# Sheet1.net
KiCad netlist of a schematic drawn in Altium Designer
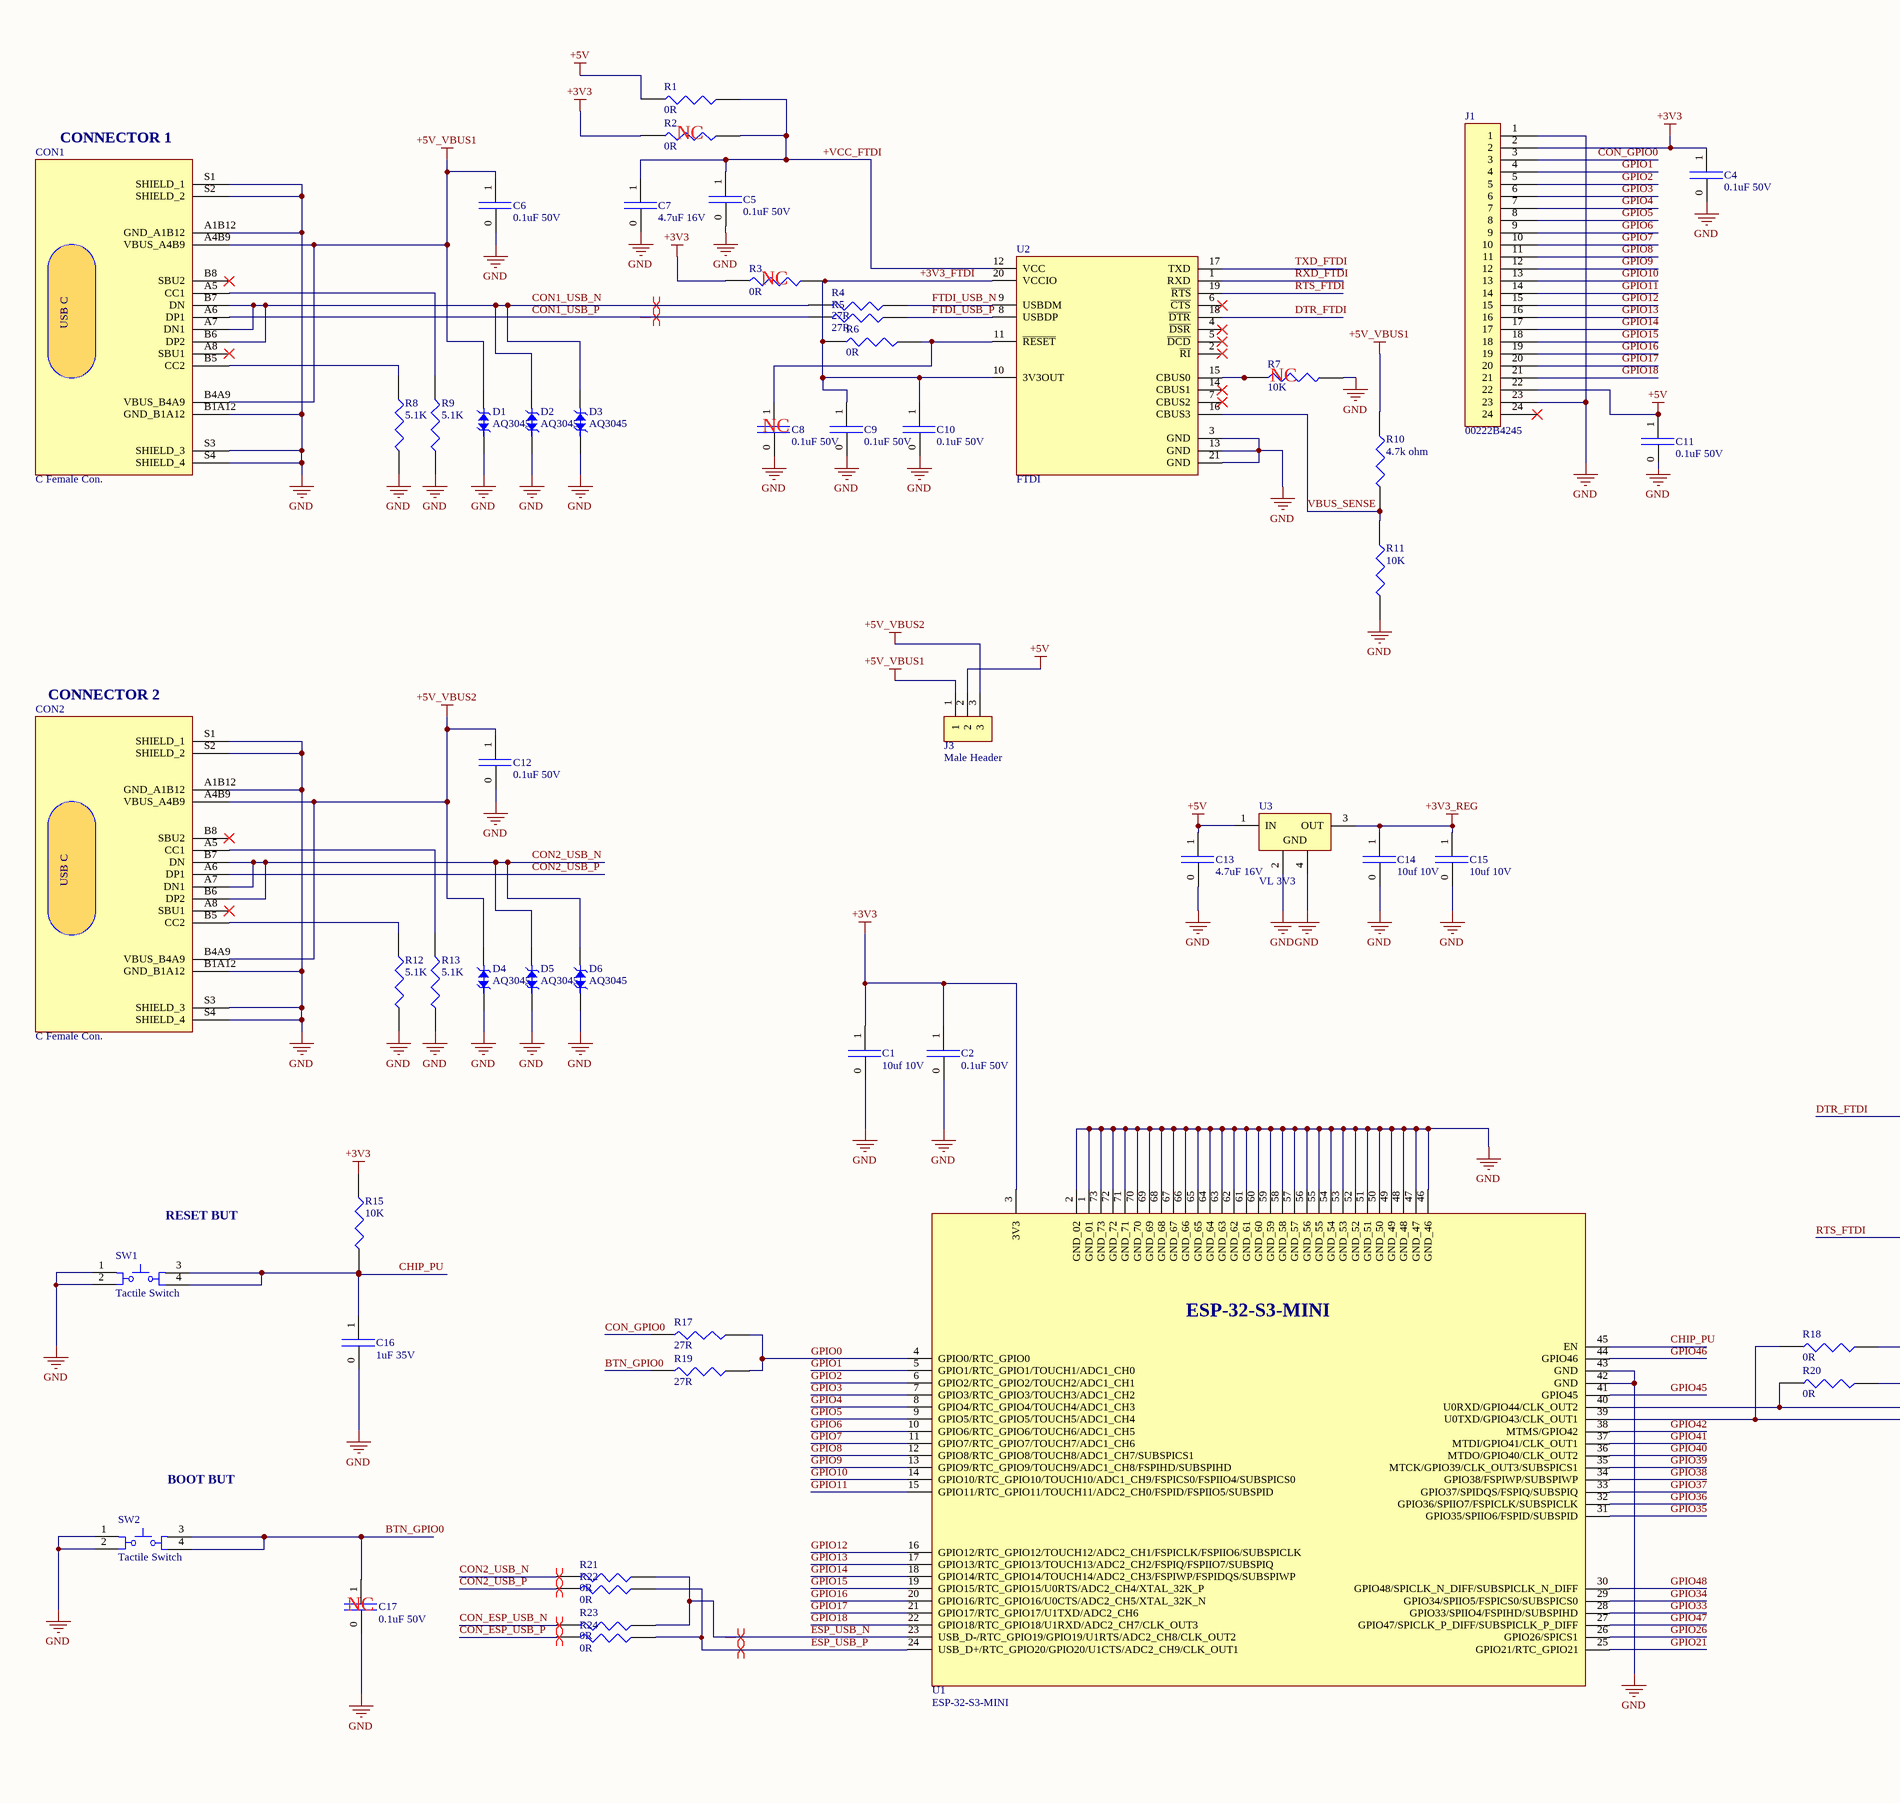
[diagram p0: Sheet1.SchDoc, left]
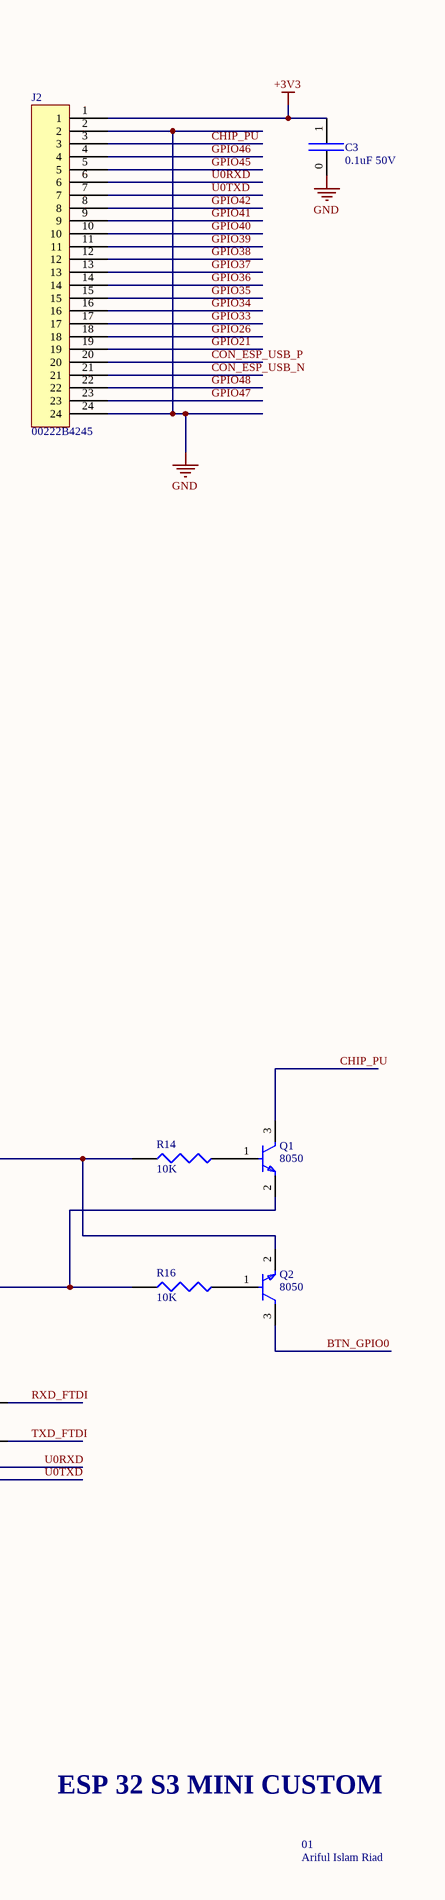
[diagram p1: Sheet1.SchDoc, right]

(export (version "E")
  (design (tool "Eeschema 10.0.6"))
  (components
    (comp (ref "C1")
      (value "10uf 10V")
      (footprint "CAPC1005X80N")
      (fields
        (field (name "MANUFACTURER") "Samsung Electro-Mechanics")
        (field (name "MANUFACTURER PART NUMBER") "CL05A106MP5NUNC")
        (field (name "TOLERANCE") "20%")
      )
      (libsource (lib "Schlib1") (part "CL05A106MP5NUNC"))
    )
    (comp (ref "C2")
      (value "0.1uF 50V")
      (footprint "CAPC1005X80N")
      (fields
        (field (name "MANUFACTURER") "Samsung Electro-Mechanics")
        (field (name "MANUFACTURER PART NUMBER") "CL05B104KB5NNWC")
        (field (name "LCSC PART NUMBER") "C7229230")
      )
      (libsource (lib "Schlib1") (part "CL05B104KB5NNWC"))
    )
    (comp (ref "C3")
      (value "0.1uF 50V")
      (footprint "CAPC1005X80N")
      (fields
        (field (name "MANUFACTURER") "Samsung Electro-Mechanics")
        (field (name "MANUFACTURER PART NUMBER") "CL05B104KB5NNWC")
        (field (name "LCSC PART NUMBER") "C7229230")
      )
      (libsource (lib "Schlib1") (part "CL05B104KB5NNWC"))
    )
    (comp (ref "C4")
      (value "0.1uF 50V")
      (footprint "CAPC1005X80N")
      (fields
        (field (name "MANUFACTURER") "Samsung Electro-Mechanics")
        (field (name "MANUFACTURER PART NUMBER") "CL05B104KB5NNWC")
        (field (name "LCSC PART NUMBER") "C7229230")
      )
      (libsource (lib "Schlib1") (part "CL05B104KB5NNWC"))
    )
    (comp (ref "C5")
      (value "0.1uF 50V")
      (footprint "CAPC1005X80N")
      (fields
        (field (name "MANUFACTURER") "Samsung Electro-Mechanics")
        (field (name "MANUFACTURER PART NUMBER") "CL05B104KB5NNWC")
        (field (name "LCSC PART NUMBER") "C7229230")
      )
      (libsource (lib "Schlib1") (part "CL05B104KB5NNWC"))
    )
    (comp (ref "C6")
      (value "0.1uF 50V")
      (footprint "CAPC1005X80N")
      (fields
        (field (name "MANUFACTURER") "Samsung Electro-Mechanics")
        (field (name "MANUFACTURER PART NUMBER") "CL05B104KB5NNWC")
        (field (name "LCSC PART NUMBER") "C7229230")
      )
      (libsource (lib "Schlib1") (part "CL05B104KB5NNWC"))
    )
    (comp (ref "C7")
      (value "4.7uF 16V")
      (footprint "CAPC1005X80N")
      (fields
        (field (name "MANUFACTURER") "Samsung Electro-Mechanics")
        (field (name "MANUFACTURER PART NUMBER") "CL05A475MO5NUNC")
        (field (name "TOLERANCE") "20%")
      )
      (libsource (lib "Schlib1") (part "CL05A475MO5NUNC"))
    )
    (comp (ref "C8")
      (value "0.1uF 50V")
      (footprint "CAPC1005X80N")
      (fields
        (field (name "MANUFACTURER") "Samsung Electro-Mechanics")
        (field (name "MANUFACTURER PART NUMBER") "CL05B104KB5NNWC")
        (field (name "LCSC PART NUMBER") "C7229230")
      )
      (libsource (lib "Schlib1") (part "CL05B104KB5NNWC"))
    )
    (comp (ref "C9")
      (value "0.1uF 50V")
      (footprint "CAPC1005X80N")
      (fields
        (field (name "MANUFACTURER") "Samsung Electro-Mechanics")
        (field (name "MANUFACTURER PART NUMBER") "CL05B104KB5NNWC")
        (field (name "LCSC PART NUMBER") "C7229230")
      )
      (libsource (lib "Schlib1") (part "CL05B104KB5NNWC"))
    )
    (comp (ref "C10")
      (value "0.1uF 50V")
      (footprint "CAPC1005X80N")
      (fields
        (field (name "MANUFACTURER") "Samsung Electro-Mechanics")
        (field (name "MANUFACTURER PART NUMBER") "CL05B104KB5NNWC")
        (field (name "LCSC PART NUMBER") "C7229230")
      )
      (libsource (lib "Schlib1") (part "CL05B104KB5NNWC"))
    )
    (comp (ref "C11")
      (value "0.1uF 50V")
      (footprint "CAPC1005X80N")
      (fields
        (field (name "MANUFACTURER") "Samsung Electro-Mechanics")
        (field (name "MANUFACTURER PART NUMBER") "CL05B104KB5NNWC")
        (field (name "LCSC PART NUMBER") "C7229230")
      )
      (libsource (lib "Schlib1") (part "CL05B104KB5NNWC"))
    )
    (comp (ref "C12")
      (value "0.1uF 50V")
      (footprint "CAPC1005X80N")
      (fields
        (field (name "MANUFACTURER") "Samsung Electro-Mechanics")
        (field (name "MANUFACTURER PART NUMBER") "CL05B104KB5NNWC")
        (field (name "LCSC PART NUMBER") "C7229230")
      )
      (libsource (lib "Schlib1") (part "CL05B104KB5NNWC"))
    )
    (comp (ref "C13")
      (value "4.7uF 16V")
      (footprint "CAPC1005X80N")
      (fields
        (field (name "MANUFACTURER") "Samsung Electro-Mechanics")
        (field (name "MANUFACTURER PART NUMBER") "CL05A475MO5NUNC")
        (field (name "TOLERANCE") "20%")
      )
      (libsource (lib "Schlib1") (part "CL05A475MO5NUNC"))
    )
    (comp (ref "C14")
      (value "10uf 10V")
      (footprint "CAPC1005X80N")
      (fields
        (field (name "MANUFACTURER") "Samsung Electro-Mechanics")
        (field (name "MANUFACTURER PART NUMBER") "CL05A106MP5NUNC")
        (field (name "TOLERANCE") "20%")
      )
      (libsource (lib "Schlib1") (part "CL05A106MP5NUNC"))
    )
    (comp (ref "C15")
      (value "10uf 10V")
      (footprint "CAPC1005X80N")
      (fields
        (field (name "MANUFACTURER") "Samsung Electro-Mechanics")
        (field (name "MANUFACTURER PART NUMBER") "CL05A106MP5NUNC")
        (field (name "TOLERANCE") "20%")
      )
      (libsource (lib "Schlib1") (part "CL05A106MP5NUNC"))
    )
    (comp (ref "C16")
      (value "1uF 35V")
      (footprint "CAPC1005X80N")
      (fields
        (field (name "MANUFACTURER") "Samsung Electro-Mechanics")
        (field (name "MANUFACTURER PART NUMBER") "CL05A105KL5NRNC")
        (field (name "TOLERANCE") "10%")
      )
      (libsource (lib "Schlib1") (part "CL05A105KL5NRNC"))
    )
    (comp (ref "C17")
      (value "0.1uF 50V")
      (footprint "CAPC1005X80N")
      (fields
        (field (name "MANUFACTURER") "Samsung Electro-Mechanics")
        (field (name "MANUFACTURER PART NUMBER") "CL05B104KB5NNWC")
        (field (name "LCSC PART NUMBER") "C7229230")
      )
      (libsource (lib "Schlib1") (part "CL05B104KB5NNWC"))
    )
    (comp (ref "CON1")
      (value "C Female Con.")
      (footprint "FP-2171790001-MFG")
      (description "USB Connector, USB Type C, USB 2.0, Receptacle, 16 Ways, Surface Mount, Through Hole Mount")
      (fields (field (name "MANUFACTURER") "Molex") (field (name "MANUFACTURER PART NUMBER") "217179-0001"))
      (libsource (lib "Schlib1") (part "217179-0001"))
    )
    (comp (ref "CON2")
      (value "C Female Con.")
      (footprint "FP-2171790001-MFG")
      (description "USB Connector, USB Type C, USB 2.0, Receptacle, 16 Ways, Surface Mount, Through Hole Mount")
      (fields (field (name "MANUFACTURER") "Molex") (field (name "MANUFACTURER PART NUMBER") "217179-0001"))
      (libsource (lib "Schlib1") (part "217179-0001"))
    )
    (comp (ref "D1")
      (value "AQ3045")
      (footprint "SOD882")
      (description "Bi 30Kv 5V 0.35Pf Automotve Tvs Sod882/ Tr Rohs Compliant: Yes ¦Littelfuse AQ3045-01ETG")
      (fields
        (field (name "MANUFACTURER") "Littelfuse")
        (field (name "MANUFACTURER PART NUMBER") "AQ3045-01ETG")
      )
      (libsource (lib "Schlib1") (part "AQ3045-01ETG"))
    )
    (comp (ref "D2")
      (value "AQ3045")
      (footprint "SOD882")
      (description "Bi 30Kv 5V 0.35Pf Automotve Tvs Sod882/ Tr Rohs Compliant: Yes ¦Littelfuse AQ3045-01ETG")
      (fields
        (field (name "MANUFACTURER") "Littelfuse")
        (field (name "MANUFACTURER PART NUMBER") "AQ3045-01ETG")
      )
      (libsource (lib "Schlib1") (part "AQ3045-01ETG"))
    )
    (comp (ref "D3")
      (value "AQ3045")
      (footprint "SOD882")
      (description "Bi 30Kv 5V 0.35Pf Automotve Tvs Sod882/ Tr Rohs Compliant: Yes ¦Littelfuse AQ3045-01ETG")
      (fields
        (field (name "MANUFACTURER") "Littelfuse")
        (field (name "MANUFACTURER PART NUMBER") "AQ3045-01ETG")
      )
      (libsource (lib "Schlib1") (part "AQ3045-01ETG"))
    )
    (comp (ref "D4")
      (value "AQ3045")
      (footprint "SOD882")
      (description "Bi 30Kv 5V 0.35Pf Automotve Tvs Sod882/ Tr Rohs Compliant: Yes ¦Littelfuse AQ3045-01ETG")
      (fields
        (field (name "MANUFACTURER") "Littelfuse")
        (field (name "MANUFACTURER PART NUMBER") "AQ3045-01ETG")
      )
      (libsource (lib "Schlib1") (part "AQ3045-01ETG"))
    )
    (comp (ref "D5")
      (value "AQ3045")
      (footprint "SOD882")
      (description "Bi 30Kv 5V 0.35Pf Automotve Tvs Sod882/ Tr Rohs Compliant: Yes ¦Littelfuse AQ3045-01ETG")
      (fields
        (field (name "MANUFACTURER") "Littelfuse")
        (field (name "MANUFACTURER PART NUMBER") "AQ3045-01ETG")
      )
      (libsource (lib "Schlib1") (part "AQ3045-01ETG"))
    )
    (comp (ref "D6")
      (value "AQ3045")
      (footprint "SOD882")
      (description "Bi 30Kv 5V 0.35Pf Automotve Tvs Sod882/ Tr Rohs Compliant: Yes ¦Littelfuse AQ3045-01ETG")
      (fields
        (field (name "MANUFACTURER") "Littelfuse")
        (field (name "MANUFACTURER PART NUMBER") "AQ3045-01ETG")
      )
      (libsource (lib "Schlib1") (part "AQ3045-01ETG"))
    )
    (comp (ref "J1")
      (value "00222B4245")
      (footprint "HDR_1x24")
      (description "Conn Unshrouded Header HDR 24 POS 2.54mm Solder ST Thru-Hole KK® Bag")
      (fields (field (name "MANUFACTURER") "Molex") (field (name "MANUFACTURER PART NUMBER") "22-28-4245"))
      (libsource (lib "Schlib1") (part "00222B4245"))
    )
    (comp (ref "J2")
      (value "00222B4245")
      (footprint "HDR_1x24")
      (description "Conn Unshrouded Header HDR 24 POS 2.54mm Solder ST Thru-Hole KK® Bag")
      (fields (field (name "MANUFACTURER") "Molex") (field (name "MANUFACTURER PART NUMBER") "22-28-4245"))
      (libsource (lib "Schlib1") (part "00222B4245"))
    )
    (comp (ref "J3")
      (value "Male Header")
      (footprint "HDR_1X3")
      (description "Pin Header, Wire-to-Board, 1.27 mm, 1 Rows, 3 Contacts, Through Hole, FTS")
      (fields
        (field (name "MANUFACTURER") "Samtec")
        (field (name "MANUFACTURER PART NUMBER") "FTS-103-01-F-S")
      )
      (libsource (lib "Schlib1") (part "FTS-103-01-F-S"))
    )
    (comp (ref "Q1")
      (value "8050")
      (footprint "FP-SS8050-G-IPC_B")
      (description "Trans Gp Bjt NPN 25V 1.5A 300MW 3-PIN SOT-23 T/r")
      (fields (field (name "MANUFACTURER") "Comchip") (field (name "MANUFACTURER PART NUMBER") "SS8050-G"))
      (libsource (lib "Schlib1") (part "SS8050-G"))
    )
    (comp (ref "Q2")
      (value "8050")
      (footprint "FP-SS8050-G-IPC_B")
      (description "Trans Gp Bjt NPN 25V 1.5A 300MW 3-PIN SOT-23 T/r")
      (fields (field (name "MANUFACTURER") "Comchip") (field (name "MANUFACTURER PART NUMBER") "SS8050-G"))
      (libsource (lib "Schlib1") (part "SS8050-G"))
    )
    (comp (ref "R1")
      (value "0R")
      (footprint "RESC1005X40N")
      (description "Zero Ohm Resistor, Jumper, 0402 [1005 Metric], Thick Film, 62.5 mW, 1 A, Surface Mount")
      (fields
        (field (name "MANUFACTURER") "Samsung Electro-Mechanics")
        (field (name "MANUFACTURER PART NUMBER") "RC1005J000CS")
      )
      (libsource (lib "Schlib1") (part "RC1005J000CS"))
    )
    (comp (ref "R2")
      (value "0R")
      (footprint "RESC1005X40N")
      (description "Zero Ohm Resistor, Jumper, 0402 [1005 Metric], Thick Film, 62.5 mW, 1 A, Surface Mount")
      (fields
        (field (name "MANUFACTURER") "Samsung Electro-Mechanics")
        (field (name "MANUFACTURER PART NUMBER") "RC1005J000CS")
      )
      (libsource (lib "Schlib1") (part "RC1005J000CS"))
    )
    (comp (ref "R3")
      (value "0R")
      (footprint "RESC1005X40N")
      (description "Zero Ohm Resistor, Jumper, 0402 [1005 Metric], Thick Film, 62.5 mW, 1 A, Surface Mount")
      (fields
        (field (name "MANUFACTURER") "Samsung Electro-Mechanics")
        (field (name "MANUFACTURER PART NUMBER") "RC1005J000CS")
      )
      (libsource (lib "Schlib1") (part "RC1005J000CS"))
    )
    (comp (ref "R4")
      (value "27R")
      (footprint "RESC1005X40N")
      (description "RC Series 0402 0.063 W 27 Ohm ±1% ±100 ppm/°C SMT Thick Film Chip Resistor")
      (fields
        (field (name "MANUFACTURER") "Yageo Group")
        (field (name "MANUFACTURER PART NUMBER") "RC0402FR-0727RL")
      )
      (libsource (lib "Schlib1") (part "RC0402FR-0727RL"))
    )
    (comp (ref "R5")
      (value "27R")
      (footprint "RESC1005X40N")
      (description "RC Series 0402 0.063 W 27 Ohm ±1% ±100 ppm/°C SMT Thick Film Chip Resistor")
      (fields
        (field (name "MANUFACTURER") "Yageo Group")
        (field (name "MANUFACTURER PART NUMBER") "RC0402FR-0727RL")
      )
      (libsource (lib "Schlib1") (part "RC0402FR-0727RL"))
    )
    (comp (ref "R6")
      (value "0R")
      (footprint "RESC1005X40N")
      (description "Zero Ohm Resistor, Jumper, 0402 [1005 Metric], Thick Film, 62.5 mW, 1 A, Surface Mount")
      (fields
        (field (name "MANUFACTURER") "Samsung Electro-Mechanics")
        (field (name "MANUFACTURER PART NUMBER") "RC1005J000CS")
      )
      (libsource (lib "Schlib1") (part "RC1005J000CS"))
    )
    (comp (ref "R7")
      (value "10K")
      (footprint "RESC1005X40N")
      (description "62.5mW Thick Film Resistors 50V ±100ppm/℃ ±1% 1kΩ 0402 Chip Resistor - Surface Mount ROHS")
      (fields
        (field (name "MANUFACTURER") "Yageo Group")
        (field (name "MANUFACTURER PART NUMBER") "RC0402FR-071KL")
      )
      (libsource (lib "Schlib1") (part "RC0402FR-071KL"))
    )
    (comp (ref "R8")
      (value "5.1K")
      (footprint "RESC1005X40N")
      (description "Res Thick Film 0402 5.1K Ohm 1% 0.063W(1/16W) ±100ppm/C Pad SMD T/R")
      (fields
        (field (name "MANUFACTURER") "Yageo Group")
        (field (name "MANUFACTURER PART NUMBER") "RC0402FR-135K1L")
      )
      (libsource (lib "Schlib1") (part "RC0402FR-135K1L"))
    )
    (comp (ref "R9")
      (value "5.1K")
      (footprint "RESC1005X40N")
      (description "Res Thick Film 0402 5.1K Ohm 1% 0.063W(1/16W) ±100ppm/C Pad SMD T/R")
      (fields
        (field (name "MANUFACTURER") "Yageo Group")
        (field (name "MANUFACTURER PART NUMBER") "RC0402FR-135K1L")
      )
      (libsource (lib "Schlib1") (part "RC0402FR-135K1L"))
    )
    (comp (ref "R10")
      (value "4.7k ohm")
      (footprint "RESC1005X40N")
      (description "Res Thick Film 1.0 x 0.5 mm 47K Ohm 5% 0.063W(1/16W) 100ppm/ C Molded SMD Paper T/R")
      (fields
        (field (name "MANUFACTURER") "Yageo Group")
        (field (name "MANUFACTURER PART NUMBER") "RC0402JR-0747KL")
      )
      (libsource (lib "Schlib1") (part "RC0402JR-0747KL"))
    )
    (comp (ref "R11")
      (value "10K")
      (footprint "RESC1005X40N")
      (description "62.5mW Thick Film Resistors 50V ±100ppm/℃ ±1% 1kΩ 0402 Chip Resistor - Surface Mount ROHS")
      (fields
        (field (name "MANUFACTURER") "Yageo Group")
        (field (name "MANUFACTURER PART NUMBER") "RC0402FR-071KL")
      )
      (libsource (lib "Schlib1") (part "RC0402FR-071KL"))
    )
    (comp (ref "R12")
      (value "5.1K")
      (footprint "RESC1005X40N")
      (description "Res Thick Film 0402 5.1K Ohm 1% 0.063W(1/16W) ±100ppm/C Pad SMD T/R")
      (fields
        (field (name "MANUFACTURER") "Yageo Group")
        (field (name "MANUFACTURER PART NUMBER") "RC0402FR-135K1L")
      )
      (libsource (lib "Schlib1") (part "RC0402FR-135K1L"))
    )
    (comp (ref "R13")
      (value "5.1K")
      (footprint "RESC1005X40N")
      (description "Res Thick Film 0402 5.1K Ohm 1% 0.063W(1/16W) ±100ppm/C Pad SMD T/R")
      (fields
        (field (name "MANUFACTURER") "Yageo Group")
        (field (name "MANUFACTURER PART NUMBER") "RC0402FR-135K1L")
      )
      (libsource (lib "Schlib1") (part "RC0402FR-135K1L"))
    )
    (comp (ref "R14")
      (value "10K")
      (footprint "RESC1005X40N")
      (description "62.5mW Thick Film Resistors 50V ±100ppm/℃ ±1% 1kΩ 0402 Chip Resistor - Surface Mount ROHS")
      (fields
        (field (name "MANUFACTURER") "Yageo Group")
        (field (name "MANUFACTURER PART NUMBER") "RC0402FR-071KL")
      )
      (libsource (lib "Schlib1") (part "RC0402FR-071KL"))
    )
    (comp (ref "R15")
      (value "10K")
      (footprint "RESC1005X40N")
      (description "62.5mW Thick Film Resistors 50V ±100ppm/℃ ±1% 1kΩ 0402 Chip Resistor - Surface Mount ROHS")
      (fields
        (field (name "MANUFACTURER") "Yageo Group")
        (field (name "MANUFACTURER PART NUMBER") "RC0402FR-071KL")
      )
      (libsource (lib "Schlib1") (part "RC0402FR-071KL"))
    )
    (comp (ref "R16")
      (value "10K")
      (footprint "RESC1005X40N")
      (description "62.5mW Thick Film Resistors 50V ±100ppm/℃ ±1% 1kΩ 0402 Chip Resistor - Surface Mount ROHS")
      (fields
        (field (name "MANUFACTURER") "Yageo Group")
        (field (name "MANUFACTURER PART NUMBER") "RC0402FR-071KL")
      )
      (libsource (lib "Schlib1") (part "RC0402FR-071KL"))
    )
    (comp (ref "R17")
      (value "27R")
      (footprint "RESC1005X40N")
      (description "RC Series 0402 0.063 W 27 Ohm ±1% ±100 ppm/°C SMT Thick Film Chip Resistor")
      (fields
        (field (name "MANUFACTURER") "Yageo Group")
        (field (name "MANUFACTURER PART NUMBER") "RC0402FR-0727RL")
      )
      (libsource (lib "Schlib1") (part "RC0402FR-0727RL"))
    )
    (comp (ref "R18")
      (value "0R")
      (footprint "RESC1005X40N")
      (description "Zero Ohm Resistor, Jumper, 0402 [1005 Metric], Thick Film, 62.5 mW, 1 A, Surface Mount")
      (fields
        (field (name "MANUFACTURER") "Samsung Electro-Mechanics")
        (field (name "MANUFACTURER PART NUMBER") "RC1005J000CS")
      )
      (libsource (lib "Schlib1") (part "RC1005J000CS"))
    )
    (comp (ref "R19")
      (value "27R")
      (footprint "RESC1005X40N")
      (description "RC Series 0402 0.063 W 27 Ohm ±1% ±100 ppm/°C SMT Thick Film Chip Resistor")
      (fields
        (field (name "MANUFACTURER") "Yageo Group")
        (field (name "MANUFACTURER PART NUMBER") "RC0402FR-0727RL")
      )
      (libsource (lib "Schlib1") (part "RC0402FR-0727RL"))
    )
    (comp (ref "R20")
      (value "0R")
      (footprint "RESC1005X40N")
      (description "Zero Ohm Resistor, Jumper, 0402 [1005 Metric], Thick Film, 62.5 mW, 1 A, Surface Mount")
      (fields
        (field (name "MANUFACTURER") "Samsung Electro-Mechanics")
        (field (name "MANUFACTURER PART NUMBER") "RC1005J000CS")
      )
      (libsource (lib "Schlib1") (part "RC1005J000CS"))
    )
    (comp (ref "R21")
      (value "0R")
      (footprint "RESC1005X40N")
      (description "Zero Ohm Resistor, Jumper, 0402 [1005 Metric], Thick Film, 62.5 mW, 1 A, Surface Mount")
      (fields
        (field (name "MANUFACTURER") "Samsung Electro-Mechanics")
        (field (name "MANUFACTURER PART NUMBER") "RC1005J000CS")
      )
      (libsource (lib "Schlib1") (part "RC1005J000CS"))
    )
    (comp (ref "R22")
      (value "0R")
      (footprint "RESC1005X40N")
      (description "Zero Ohm Resistor, Jumper, 0402 [1005 Metric], Thick Film, 62.5 mW, 1 A, Surface Mount")
      (fields
        (field (name "MANUFACTURER") "Samsung Electro-Mechanics")
        (field (name "MANUFACTURER PART NUMBER") "RC1005J000CS")
      )
      (libsource (lib "Schlib1") (part "RC1005J000CS"))
    )
    (comp (ref "R23")
      (value "0R")
      (footprint "RESC1005X40N")
      (description "Zero Ohm Resistor, Jumper, 0402 [1005 Metric], Thick Film, 62.5 mW, 1 A, Surface Mount")
      (fields
        (field (name "MANUFACTURER") "Samsung Electro-Mechanics")
        (field (name "MANUFACTURER PART NUMBER") "RC1005J000CS")
      )
      (libsource (lib "Schlib1") (part "RC1005J000CS"))
    )
    (comp (ref "R24")
      (value "0R")
      (footprint "RESC1005X40N")
      (description "Zero Ohm Resistor, Jumper, 0402 [1005 Metric], Thick Film, 62.5 mW, 1 A, Surface Mount")
      (fields
        (field (name "MANUFACTURER") "Samsung Electro-Mechanics")
        (field (name "MANUFACTURER PART NUMBER") "RC1005J000CS")
      )
      (libsource (lib "Schlib1") (part "RC1005J000CS"))
    )
    (comp (ref "SW1")
      (value "Tactile Switch")
      (footprint "ESWI-TL3301NF160QG_V")
      (description "Switch Tactile N.O. SPST Round Button Gull Wing 0.05A 12VDC 100000Cycles 1.57N SMD T/R")
      (fields
        (field (name "MANUFACTURER") "E-Switch")
        (field (name "MANUFACTURER PART NUMBER") "TL3301NF160QG")
      )
      (libsource (lib "Schlib1") (part "TL3301NF160QG"))
    )
    (comp (ref "SW2")
      (value "Tactile Switch")
      (footprint "ESWI-TL3301NF160QG_V")
      (description "Switch Tactile N.O. SPST Round Button Gull Wing 0.05A 12VDC 100000Cycles 1.57N SMD T/R")
      (fields
        (field (name "MANUFACTURER") "E-Switch")
        (field (name "MANUFACTURER PART NUMBER") "TL3301NF160QG")
      )
      (libsource (lib "Schlib1") (part "TL3301NF160QG"))
    )
    (comp (ref "U1")
      (value "ESP-32-S3-MINI")
      (footprint "XCVR_ESP32-S3-MINI-1-N8")
      (description "20.5dBm ESP32-S3FN8 Chip 2.4GHz SMD WiFi Modules ROHS")
      (fields
        (field (name "MANUFACTURER") "Espressif Systems")
        (field (name "MANUFACTURER PART NUMBER") "ESP32-S3-MINI-1-N8")
      )
      (libsource (lib "Schlib1") (part "ESP32-S3-MINI-1-N8"))
    )
    (comp (ref "U2")
      (value "FTDI")
      (footprint "FP-QFN-20-IPC_B")
      (description "Tape & Reel (TR) 2006 UART USB 2.0 interface controller 3.3V~5V 4mm 8mA 12Mbps")
      (fields
        (field (name "MANUFACTURER PART NUMBER") "FT231XQ-R")
        (field (name "LCSC PART NUMBER") "C1521552")
      )
      (libsource (lib "Schlib1") (part "FT231XQ-R"))
    )
    (comp (ref "U3")
      (value "VL 3V3")
      (footprint "DCY0004A_N")
      (description "1.5-A, 20-V, low-dropout voltage regulator with reverse current & reverse voltage protection")
      (fields
        (field (name "MANUFACTURER") "Texas Instruments")
        (field (name "MANUFACTURER PART NUMBER") "TL1963A-33DCYR")
      )
      (libsource (lib "Schlib1") (part "TL1963A-33DCYR"))
    )
  )
  (nets
    (net (code "1") (name "+3V3") (class "Default")
      (node (ref "C1") (pin "1") (pinfunction "1_1") (pintype "passive"))
      (node (ref "C2") (pin "1") (pinfunction "1_1") (pintype "passive"))
      (node (ref "C3") (pin "1") (pinfunction "1_1") (pintype "passive"))
      (node (ref "C4") (pin "1") (pinfunction "1_1") (pintype "passive"))
      (node (ref "J1") (pin "2") (pinfunction "2_2") (pintype "passive"))
      (node (ref "J2") (pin "1") (pinfunction "1_1") (pintype "passive"))
      (node (ref "R15") (pin "3") (pinfunction "3_3") (pintype "passive"))
      (node (ref "R2") (pin "2") (pinfunction "2_2") (pintype "passive"))
      (node (ref "R3") (pin "2") (pinfunction "2_2") (pintype "passive"))
      (node (ref "U1") (pin "3") (pinfunction "3V3_3") (pintype "passive"))
    )
    (net (code "2") (name "+3V3_REG") (class "Default")
      (node (ref "C14") (pin "1") (pinfunction "1_1") (pintype "passive"))
      (node (ref "C15") (pin "1") (pinfunction "1_1") (pintype "passive"))
      (node (ref "U3") (pin "3") (pinfunction "OUT_3") (pintype "power_in"))
    )
    (net (code "3") (name "+5V") (class "Default")
      (node (ref "C11") (pin "1") (pinfunction "1_1") (pintype "passive"))
      (node (ref "C13") (pin "1") (pinfunction "1_1") (pintype "passive"))
      (node (ref "J1") (pin "22") (pinfunction "22_22") (pintype "passive"))
      (node (ref "J3") (pin "2") (pinfunction "2_2") (pintype "passive"))
      (node (ref "R1") (pin "2") (pinfunction "2_2") (pintype "passive"))
      (node (ref "U3") (pin "1") (pinfunction "IN_1") (pintype "power_in"))
    )
    (net (code "4") (name "+5V_VBUS1") (class "Default")
      (node (ref "C6") (pin "1") (pinfunction "1_1") (pintype "passive"))
      (node (ref "CON1") (pin "A4B9") (pinfunction "VBUS_A4B9_A4B9") (pintype "passive"))
      (node (ref "CON1") (pin "B4A9") (pinfunction "VBUS_B4A9_B4A9") (pintype "passive"))
      (node (ref "D1") (pin "B10") (pinfunction "B10_B10") (pintype "passive"))
      (node (ref "J3") (pin "1") (pinfunction "1_1") (pintype "passive"))
      (node (ref "R10") (pin "3") (pinfunction "3_3") (pintype "passive"))
    )
    (net (code "5") (name "+5V_VBUS2") (class "Default")
      (node (ref "C12") (pin "1") (pinfunction "1_1") (pintype "passive"))
      (node (ref "CON2") (pin "A4B9") (pinfunction "VBUS_A4B9_A4B9") (pintype "passive"))
      (node (ref "CON2") (pin "B4A9") (pinfunction "VBUS_B4A9_B4A9") (pintype "passive"))
      (node (ref "D4") (pin "B10") (pinfunction "B10_B10") (pintype "passive"))
      (node (ref "J3") (pin "3") (pinfunction "3_3") (pintype "passive"))
    )
    (net (code "6") (name "/+3V3_FTDI") (class "Default")
      (node (ref "C10") (pin "1") (pinfunction "1_1") (pintype "passive"))
      (node (ref "C9") (pin "1") (pinfunction "1_1") (pintype "passive"))
      (node (ref "R3") (pin "3") (pinfunction "3_3") (pintype "passive"))
      (node (ref "R6") (pin "2") (pinfunction "2_2") (pintype "passive"))
      (node (ref "U2") (pin "10") (pinfunction "3V3OUT_10") (pintype "passive"))
      (node (ref "U2") (pin "20") (pinfunction "VCCIO_20") (pintype "passive"))
    )
    (net (code "7") (name "/+VCC_FTDI") (class "Default")
      (node (ref "C5") (pin "1") (pinfunction "1_1") (pintype "passive"))
      (node (ref "C7") (pin "1") (pinfunction "1_1") (pintype "passive"))
      (node (ref "R1") (pin "3") (pinfunction "3_3") (pintype "passive"))
      (node (ref "R2") (pin "3") (pinfunction "3_3") (pintype "passive"))
      (node (ref "U2") (pin "12") (pinfunction "VCC_12") (pintype "passive"))
    )
    (net (code "8") (name "/BTN_GPIO0") (class "Default")
      (node (ref "C17") (pin "1") (pinfunction "1_1") (pintype "passive"))
      (node (ref "Q2") (pin "3") (pinfunction "C_3") (pintype "passive"))
      (node (ref "R19") (pin "2") (pinfunction "2_2") (pintype "passive"))
      (node (ref "SW2") (pin "3") (pinfunction "3_3") (pintype "passive"))
      (node (ref "SW2") (pin "4") (pinfunction "4_4") (pintype "passive"))
    )
    (net (code "9") (name "/CHIP_PU") (class "Default")
      (node (ref "C16") (pin "1") (pinfunction "1_1") (pintype "passive"))
      (node (ref "J2") (pin "3") (pinfunction "3_3") (pintype "passive"))
      (node (ref "Q1") (pin "3") (pinfunction "C_3") (pintype "passive"))
      (node (ref "R15") (pin "2") (pinfunction "2_2") (pintype "passive"))
      (node (ref "SW1") (pin "3") (pinfunction "3_3") (pintype "passive"))
      (node (ref "SW1") (pin "4") (pinfunction "4_4") (pintype "passive"))
      (node (ref "U1") (pin "45") (pinfunction "EN_45") (pintype "passive"))
    )
    (net (code "10") (name "/CON1_USB_N") (class "Default")
      (node (ref "CON1") (pin "A7") (pinfunction "DN1_A7") (pintype "passive"))
      (node (ref "CON1") (pin "B6") (pinfunction "DP2_B6") (pintype "passive"))
      (node (ref "CON1") (pin "B7") (pinfunction "DN_B7") (pintype "passive"))
      (node (ref "D2") (pin "B10") (pinfunction "B10_B10") (pintype "passive"))
      (node (ref "D3") (pin "B10") (pinfunction "B10_B10") (pintype "passive"))
      (node (ref "R4") (pin "2") (pinfunction "2_2") (pintype "passive"))
    )
    (net (code "11") (name "/CON1_USB_P") (class "Default")
      (node (ref "CON1") (pin "A6") (pinfunction "DP1_A6") (pintype "passive"))
      (node (ref "R5") (pin "2") (pinfunction "2_2") (pintype "passive"))
    )
    (net (code "12") (name "/CON2_USB_N") (class "Default")
      (node (ref "CON2") (pin "A7") (pinfunction "DN1_A7") (pintype "passive"))
      (node (ref "CON2") (pin "B6") (pinfunction "DP2_B6") (pintype "passive"))
      (node (ref "CON2") (pin "B7") (pinfunction "DN_B7") (pintype "passive"))
      (node (ref "D5") (pin "B10") (pinfunction "B10_B10") (pintype "passive"))
      (node (ref "D6") (pin "B10") (pinfunction "B10_B10") (pintype "passive"))
      (node (ref "R21") (pin "2") (pinfunction "2_2") (pintype "passive"))
    )
    (net (code "13") (name "/CON2_USB_P") (class "Default")
      (node (ref "CON2") (pin "A6") (pinfunction "DP1_A6") (pintype "passive"))
      (node (ref "R22") (pin "2") (pinfunction "2_2") (pintype "passive"))
    )
    (net (code "14") (name "/CON_ESP_USB_N") (class "Default")
      (node (ref "J2") (pin "21") (pinfunction "21_21") (pintype "passive"))
      (node (ref "R23") (pin "2") (pinfunction "2_2") (pintype "passive"))
    )
    (net (code "15") (name "/CON_ESP_USB_P") (class "Default")
      (node (ref "J2") (pin "20") (pinfunction "20_20") (pintype "passive"))
      (node (ref "R24") (pin "2") (pinfunction "2_2") (pintype "passive"))
    )
    (net (code "16") (name "/CON_GPIO0") (class "Default")
      (node (ref "J1") (pin "3") (pinfunction "3_3") (pintype "passive"))
      (node (ref "R17") (pin "2") (pinfunction "2_2") (pintype "passive"))
    )
    (net (code "17") (name "/DTR_FTDI") (class "Default")
      (node (ref "Q2") (pin "2") (pinfunction "E_2") (pintype "passive"))
      (node (ref "R14") (pin "3") (pinfunction "3_3") (pintype "passive"))
      (node (ref "U2") (pin "18") (pinfunction "~{DTR}_18") (pintype "passive"))
    )
    (net (code "18") (name "/ESP_USB_N") (class "Default")
      (node (ref "R21") (pin "3") (pinfunction "3_3") (pintype "passive"))
      (node (ref "R23") (pin "3") (pinfunction "3_3") (pintype "passive"))
      (node (ref "U1") (pin "23") (pinfunction "USB_D-/RTC_GPIO19/GPIO19/U1RTS/ADC2_CH8/CLK_OUT2_23") (pintype "passive"))
    )
    (net (code "19") (name "/ESP_USB_P") (class "Default")
      (node (ref "R22") (pin "3") (pinfunction "3_3") (pintype "passive"))
      (node (ref "R24") (pin "3") (pinfunction "3_3") (pintype "passive"))
      (node (ref "U1") (pin "24") (pinfunction "USB_D+/RTC_GPIO20/GPIO20/U1CTS/ADC2_CH9/CLK_OUT1_24") (pintype "passive"))
    )
    (net (code "20") (name "/FTDI_USB_N") (class "Default")
      (node (ref "R4") (pin "3") (pinfunction "3_3") (pintype "passive"))
      (node (ref "U2") (pin "9") (pinfunction "USBDM_9") (pintype "passive"))
    )
    (net (code "21") (name "/FTDI_USB_P") (class "Default")
      (node (ref "R5") (pin "3") (pinfunction "3_3") (pintype "passive"))
      (node (ref "U2") (pin "8") (pinfunction "USBDP_8") (pintype "passive"))
    )
    (net (code "22") (name "/GPIO0") (class "Default")
      (node (ref "R17") (pin "3") (pinfunction "3_3") (pintype "passive"))
      (node (ref "R19") (pin "3") (pinfunction "3_3") (pintype "passive"))
      (node (ref "U1") (pin "4") (pinfunction "GPIO0/RTC_GPIO0_4") (pintype "passive"))
    )
    (net (code "23") (name "/GPIO1") (class "Default")
      (node (ref "J1") (pin "4") (pinfunction "4_4") (pintype "passive"))
      (node (ref "U1") (pin "5") (pinfunction "GPIO1/RTC_GPIO1/TOUCH1/ADC1_CH0_5") (pintype "passive"))
    )
    (net (code "24") (name "/GPIO2") (class "Default")
      (node (ref "J1") (pin "5") (pinfunction "5_5") (pintype "passive"))
      (node (ref "U1") (pin "6") (pinfunction "GPIO2/RTC_GPIO2/TOUCH2/ADC1_CH1_6") (pintype "passive"))
    )
    (net (code "25") (name "/GPIO3") (class "Default")
      (node (ref "J1") (pin "6") (pinfunction "6_6") (pintype "passive"))
      (node (ref "U1") (pin "7") (pinfunction "GPIO3/RTC_GPIO3/TOUCH3/ADC1_CH2_7") (pintype "passive"))
    )
    (net (code "26") (name "/GPIO4") (class "Default")
      (node (ref "J1") (pin "7") (pinfunction "7_7") (pintype "passive"))
      (node (ref "U1") (pin "8") (pinfunction "GPIO4/RTC_GPIO4/TOUCH4/ADC1_CH3_8") (pintype "passive"))
    )
    (net (code "27") (name "/GPIO5") (class "Default")
      (node (ref "J1") (pin "8") (pinfunction "8_8") (pintype "passive"))
      (node (ref "U1") (pin "9") (pinfunction "GPIO5/RTC_GPIO5/TOUCH5/ADC1_CH4_9") (pintype "passive"))
    )
    (net (code "28") (name "/GPIO6") (class "Default")
      (node (ref "J1") (pin "9") (pinfunction "9_9") (pintype "passive"))
      (node (ref "U1") (pin "10") (pinfunction "GPIO6/RTC_GPIO6/TOUCH6/ADC1_CH5_10") (pintype "passive"))
    )
    (net (code "29") (name "/GPIO7") (class "Default")
      (node (ref "J1") (pin "10") (pinfunction "10_10") (pintype "passive"))
      (node (ref "U1") (pin "11") (pinfunction "GPIO7/RTC_GPIO7/TOUCH7/ADC1_CH6_11") (pintype "passive"))
    )
    (net (code "30") (name "/GPIO8") (class "Default")
      (node (ref "J1") (pin "11") (pinfunction "11_11") (pintype "passive"))
      (node (ref "U1") (pin "12") (pinfunction "GPIO8/RTC_GPIO8/TOUCH8/ADC1_CH7/SUBSPICS1_12") (pintype "passive"))
    )
    (net (code "31") (name "/GPIO9") (class "Default")
      (node (ref "J1") (pin "12") (pinfunction "12_12") (pintype "passive"))
      (node (ref "U1") (pin "13") (pinfunction "GPIO9/RTC_GPIO9/TOUCH9/ADC1_CH8/FSPIHD/SUBSPIHD_13") (pintype "passive"))
    )
    (net (code "32") (name "/GPIO10") (class "Default")
      (node (ref "J1") (pin "13") (pinfunction "13_13") (pintype "passive"))
      (node (ref "U1") (pin "14") (pinfunction "GPIO10/RTC_GPIO10/TOUCH10/ADC1_CH9/FSPICS0/FSPIIO4/SUBSPICS0_14") (pintype "passive"))
    )
    (net (code "33") (name "/GPIO11") (class "Default")
      (node (ref "J1") (pin "14") (pinfunction "14_14") (pintype "passive"))
      (node (ref "U1") (pin "15") (pinfunction "GPIO11/RTC_GPIO11/TOUCH11/ADC2_CH0/FSPID/FSPIIO5/SUBSPID_15") (pintype "passive"))
    )
    (net (code "34") (name "/GPIO12") (class "Default")
      (node (ref "J1") (pin "15") (pinfunction "15_15") (pintype "passive"))
      (node (ref "U1") (pin "16") (pinfunction "GPIO12/RTC_GPIO12/TOUCH12/ADC2_CH1/FSPICLK/FSPIIO6/SUBSPICLK_16") (pintype "passive"))
    )
    (net (code "35") (name "/GPIO13") (class "Default")
      (node (ref "J1") (pin "16") (pinfunction "16_16") (pintype "passive"))
      (node (ref "U1") (pin "17") (pinfunction "GPIO13/RTC_GPIO13/TOUCH13/ADC2_CH2/FSPIQ/FSPIIO7/SUBSPIQ_17") (pintype "passive"))
    )
    (net (code "36") (name "/GPIO14") (class "Default")
      (node (ref "J1") (pin "17") (pinfunction "17_17") (pintype "passive"))
      (node (ref "U1") (pin "18") (pinfunction "GPIO14/RTC_GPIO14/TOUCH14/ADC2_CH3/FSPIWP/FSPIDQS/SUBSPIWP_18") (pintype "passive"))
    )
    (net (code "37") (name "/GPIO15") (class "Default")
      (node (ref "J1") (pin "18") (pinfunction "18_18") (pintype "passive"))
      (node (ref "U1") (pin "19") (pinfunction "GPIO15/RTC_GPIO15/U0RTS/ADC2_CH4/XTAL_32K_P_19") (pintype "passive"))
    )
    (net (code "38") (name "/GPIO16") (class "Default")
      (node (ref "J1") (pin "19") (pinfunction "19_19") (pintype "passive"))
      (node (ref "U1") (pin "20") (pinfunction "GPIO16/RTC_GPIO16/U0CTS/ADC2_CH5/XTAL_32K_N_20") (pintype "passive"))
    )
    (net (code "39") (name "/GPIO17") (class "Default")
      (node (ref "J1") (pin "20") (pinfunction "20_20") (pintype "passive"))
      (node (ref "U1") (pin "21") (pinfunction "GPIO17/RTC_GPIO17/U1TXD/ADC2_CH6_21") (pintype "passive"))
    )
    (net (code "40") (name "/GPIO18") (class "Default")
      (node (ref "J1") (pin "21") (pinfunction "21_21") (pintype "passive"))
      (node (ref "U1") (pin "22") (pinfunction "GPIO18/RTC_GPIO18/U1RXD/ADC2_CH7/CLK_OUT3_22") (pintype "passive"))
    )
    (net (code "41") (name "/GPIO21") (class "Default")
      (node (ref "J2") (pin "19") (pinfunction "19_19") (pintype "passive"))
      (node (ref "U1") (pin "25") (pinfunction "GPIO21/RTC_GPIO21_25") (pintype "passive"))
    )
    (net (code "42") (name "/GPIO26") (class "Default")
      (node (ref "J2") (pin "18") (pinfunction "18_18") (pintype "passive"))
      (node (ref "U1") (pin "26") (pinfunction "GPIO26/SPICS1_26") (pintype "passive"))
    )
    (net (code "43") (name "/GPIO33") (class "Default")
      (node (ref "J2") (pin "17") (pinfunction "17_17") (pintype "passive"))
      (node (ref "U1") (pin "28") (pinfunction "GPIO33/SPIIO4/FSPIHD/SUBSPIHD_28") (pintype "passive"))
    )
    (net (code "44") (name "/GPIO34") (class "Default")
      (node (ref "J2") (pin "16") (pinfunction "16_16") (pintype "passive"))
      (node (ref "U1") (pin "29") (pinfunction "GPIO34/SPIIO5/FSPICS0/SUBSPICS0_29") (pintype "passive"))
    )
    (net (code "45") (name "/GPIO35") (class "Default")
      (node (ref "J2") (pin "15") (pinfunction "15_15") (pintype "passive"))
      (node (ref "U1") (pin "31") (pinfunction "GPIO35/SPIIO6/FSPID/SUBSPID_31") (pintype "passive"))
    )
    (net (code "46") (name "/GPIO36") (class "Default")
      (node (ref "J2") (pin "14") (pinfunction "14_14") (pintype "passive"))
      (node (ref "U1") (pin "32") (pinfunction "GPIO36/SPIIO7/FSPICLK/SUBSPICLK_32") (pintype "passive"))
    )
    (net (code "47") (name "/GPIO37") (class "Default")
      (node (ref "J2") (pin "13") (pinfunction "13_13") (pintype "passive"))
      (node (ref "U1") (pin "33") (pinfunction "GPIO37/SPIDQS/FSPIQ/SUBSPIQ_33") (pintype "passive"))
    )
    (net (code "48") (name "/GPIO38") (class "Default")
      (node (ref "J2") (pin "12") (pinfunction "12_12") (pintype "passive"))
      (node (ref "U1") (pin "34") (pinfunction "GPIO38/FSPIWP/SUBSPIWP_34") (pintype "passive"))
    )
    (net (code "49") (name "/GPIO39") (class "Default")
      (node (ref "J2") (pin "11") (pinfunction "11_11") (pintype "passive"))
      (node (ref "U1") (pin "35") (pinfunction "MTCK/GPIO39/CLK_OUT3/SUBSPICS1_35") (pintype "passive"))
    )
    (net (code "50") (name "/GPIO40") (class "Default")
      (node (ref "J2") (pin "10") (pinfunction "10_10") (pintype "passive"))
      (node (ref "U1") (pin "36") (pinfunction "MTDO/GPIO40/CLK_OUT2_36") (pintype "passive"))
    )
    (net (code "51") (name "/GPIO41") (class "Default")
      (node (ref "J2") (pin "9") (pinfunction "9_9") (pintype "passive"))
      (node (ref "U1") (pin "37") (pinfunction "MTDI/GPIO41/CLK_OUT1_37") (pintype "passive"))
    )
    (net (code "52") (name "/GPIO42") (class "Default")
      (node (ref "J2") (pin "8") (pinfunction "8_8") (pintype "passive"))
      (node (ref "U1") (pin "38") (pinfunction "MTMS/GPIO42_38") (pintype "passive"))
    )
    (net (code "53") (name "/GPIO45") (class "Default")
      (node (ref "J2") (pin "5") (pinfunction "5_5") (pintype "passive"))
      (node (ref "U1") (pin "41") (pinfunction "GPIO45_41") (pintype "passive"))
    )
    (net (code "54") (name "/GPIO46") (class "Default")
      (node (ref "J2") (pin "4") (pinfunction "4_4") (pintype "passive"))
      (node (ref "U1") (pin "44") (pinfunction "GPIO46_44") (pintype "passive"))
    )
    (net (code "55") (name "/GPIO47") (class "Default")
      (node (ref "J2") (pin "23") (pinfunction "23_23") (pintype "passive"))
      (node (ref "U1") (pin "27") (pinfunction "GPIO47/SPICLK_P_DIFF/SUBSPICLK_P_DIFF_27") (pintype "passive"))
    )
    (net (code "56") (name "/GPIO48") (class "Default")
      (node (ref "J2") (pin "22") (pinfunction "22_22") (pintype "passive"))
      (node (ref "U1") (pin "30") (pinfunction "GPIO48/SPICLK_N_DIFF/SUBSPICLK_N_DIFF_30") (pintype "passive"))
    )
    (net (code "57") (name "/RTS_FTDI") (class "Default")
      (node (ref "Q1") (pin "2") (pinfunction "E_2") (pintype "passive"))
      (node (ref "R16") (pin "3") (pinfunction "3_3") (pintype "passive"))
      (node (ref "U2") (pin "19") (pinfunction "~{RTS}_19") (pintype "passive"))
    )
    (net (code "58") (name "/RXD_FTDI") (class "Default")
      (node (ref "R18") (pin "3") (pinfunction "3_3") (pintype "passive"))
      (node (ref "U2") (pin "1") (pinfunction "RXD_1") (pintype "passive"))
    )
    (net (code "59") (name "/TXD_FTDI") (class "Default")
      (node (ref "R20") (pin "3") (pinfunction "3_3") (pintype "passive"))
      (node (ref "U2") (pin "17") (pinfunction "TXD_17") (pintype "passive"))
    )
    (net (code "60") (name "/U0RXD") (class "Default")
      (node (ref "J2") (pin "6") (pinfunction "6_6") (pintype "passive"))
      (node (ref "R20") (pin "2") (pinfunction "2_2") (pintype "passive"))
      (node (ref "U1") (pin "40") (pinfunction "U0RXD/GPIO44/CLK_OUT2_40") (pintype "passive"))
    )
    (net (code "61") (name "/U0TXD") (class "Default")
      (node (ref "J2") (pin "7") (pinfunction "7_7") (pintype "passive"))
      (node (ref "R18") (pin "2") (pinfunction "2_2") (pintype "passive"))
      (node (ref "U1") (pin "39") (pinfunction "U0TXD/GPIO43/CLK_OUT1_39") (pintype "passive"))
    )
    (net (code "62") (name "/VBUS_SENSE") (class "Default")
      (node (ref "R10") (pin "2") (pinfunction "2_2") (pintype "passive"))
      (node (ref "R11") (pin "3") (pinfunction "3_3") (pintype "passive"))
      (node (ref "U2") (pin "16") (pinfunction "CBUS3_16") (pintype "passive"))
    )
    (net (code "63") (name "GND") (class "Default")
      (node (ref "C1") (pin "0") (pinfunction "0_0") (pintype "passive"))
      (node (ref "C10") (pin "0") (pinfunction "0_0") (pintype "passive"))
      (node (ref "C11") (pin "0") (pinfunction "0_0") (pintype "passive"))
      (node (ref "C12") (pin "0") (pinfunction "0_0") (pintype "passive"))
      (node (ref "C13") (pin "0") (pinfunction "0_0") (pintype "passive"))
      (node (ref "C14") (pin "0") (pinfunction "0_0") (pintype "passive"))
      (node (ref "C15") (pin "0") (pinfunction "0_0") (pintype "passive"))
      (node (ref "C16") (pin "0") (pinfunction "0_0") (pintype "passive"))
      (node (ref "C17") (pin "0") (pinfunction "0_0") (pintype "passive"))
      (node (ref "C2") (pin "0") (pinfunction "0_0") (pintype "passive"))
      (node (ref "C3") (pin "0") (pinfunction "0_0") (pintype "passive"))
      (node (ref "C4") (pin "0") (pinfunction "0_0") (pintype "passive"))
      (node (ref "C5") (pin "0") (pinfunction "0_0") (pintype "passive"))
      (node (ref "C6") (pin "0") (pinfunction "0_0") (pintype "passive"))
      (node (ref "C7") (pin "0") (pinfunction "0_0") (pintype "passive"))
      (node (ref "C8") (pin "0") (pinfunction "0_0") (pintype "passive"))
      (node (ref "C9") (pin "0") (pinfunction "0_0") (pintype "passive"))
      (node (ref "CON1") (pin "A1B12") (pinfunction "GND_A1B12_A1B12") (pintype "passive"))
      (node (ref "CON1") (pin "B1A12") (pinfunction "GND_B1A12_B1A12") (pintype "passive"))
      (node (ref "CON1") (pin "S1") (pinfunction "SHIELD_1_S1") (pintype "passive"))
      (node (ref "CON1") (pin "S2") (pinfunction "SHIELD_2_S2") (pintype "passive"))
      (node (ref "CON1") (pin "S3") (pinfunction "SHIELD_3_S3") (pintype "passive"))
      (node (ref "CON1") (pin "S4") (pinfunction "SHIELD_4_S4") (pintype "passive"))
      (node (ref "CON2") (pin "A1B12") (pinfunction "GND_A1B12_A1B12") (pintype "passive"))
      (node (ref "CON2") (pin "B1A12") (pinfunction "GND_B1A12_B1A12") (pintype "passive"))
      (node (ref "CON2") (pin "S1") (pinfunction "SHIELD_1_S1") (pintype "passive"))
      (node (ref "CON2") (pin "S2") (pinfunction "SHIELD_2_S2") (pintype "passive"))
      (node (ref "CON2") (pin "S3") (pinfunction "SHIELD_3_S3") (pintype "passive"))
      (node (ref "CON2") (pin "S4") (pinfunction "SHIELD_4_S4") (pintype "passive"))
      (node (ref "D1") (pin "B9") (pinfunction "B9_B9") (pintype "passive"))
      (node (ref "D2") (pin "B9") (pinfunction "B9_B9") (pintype "passive"))
      (node (ref "D3") (pin "B9") (pinfunction "B9_B9") (pintype "passive"))
      (node (ref "D4") (pin "B9") (pinfunction "B9_B9") (pintype "passive"))
      (node (ref "D5") (pin "B9") (pinfunction "B9_B9") (pintype "passive"))
      (node (ref "D6") (pin "B9") (pinfunction "B9_B9") (pintype "passive"))
      (node (ref "J1") (pin "1") (pinfunction "1_1") (pintype "passive"))
      (node (ref "J1") (pin "23") (pinfunction "23_23") (pintype "passive"))
      (node (ref "J2") (pin "2") (pinfunction "2_2") (pintype "passive"))
      (node (ref "J2") (pin "24") (pinfunction "24_24") (pintype "passive"))
      (node (ref "R11") (pin "2") (pinfunction "2_2") (pintype "passive"))
      (node (ref "R12") (pin "2") (pinfunction "2_2") (pintype "passive"))
      (node (ref "R13") (pin "2") (pinfunction "2_2") (pintype "passive"))
      (node (ref "R7") (pin "2") (pinfunction "2_2") (pintype "passive"))
      (node (ref "R8") (pin "2") (pinfunction "2_2") (pintype "passive"))
      (node (ref "R9") (pin "2") (pinfunction "2_2") (pintype "passive"))
      (node (ref "SW1") (pin "1") (pinfunction "1_1") (pintype "passive"))
      (node (ref "SW1") (pin "2") (pinfunction "2_2") (pintype "passive"))
      (node (ref "SW2") (pin "1") (pinfunction "1_1") (pintype "passive"))
      (node (ref "SW2") (pin "2") (pinfunction "2_2") (pintype "passive"))
      (node (ref "U1") (pin "1") (pinfunction "GND_01_1") (pintype "passive"))
      (node (ref "U1") (pin "2") (pinfunction "GND_02_2") (pintype "passive"))
      (node (ref "U1") (pin "42") (pinfunction "GND_42") (pintype "passive"))
      (node (ref "U1") (pin "43") (pinfunction "GND_43") (pintype "passive"))
      (node (ref "U1") (pin "46") (pinfunction "GND_46_46") (pintype "passive"))
      (node (ref "U1") (pin "47") (pinfunction "GND_47_47") (pintype "passive"))
      (node (ref "U1") (pin "48") (pinfunction "GND_48_48") (pintype "passive"))
      (node (ref "U1") (pin "49") (pinfunction "GND_49_49") (pintype "passive"))
      (node (ref "U1") (pin "50") (pinfunction "GND_50_50") (pintype "passive"))
      (node (ref "U1") (pin "51") (pinfunction "GND_51_51") (pintype "passive"))
      (node (ref "U1") (pin "52") (pinfunction "GND_52_52") (pintype "passive"))
      (node (ref "U1") (pin "53") (pinfunction "GND_53_53") (pintype "passive"))
      (node (ref "U1") (pin "54") (pinfunction "GND_54_54") (pintype "passive"))
      (node (ref "U1") (pin "55") (pinfunction "GND_55_55") (pintype "passive"))
      (node (ref "U1") (pin "56") (pinfunction "GND_56_56") (pintype "passive"))
      (node (ref "U1") (pin "57") (pinfunction "GND_57_57") (pintype "passive"))
      (node (ref "U1") (pin "58") (pinfunction "GND_58_58") (pintype "passive"))
      (node (ref "U1") (pin "59") (pinfunction "GND_59_59") (pintype "passive"))
      (node (ref "U1") (pin "60") (pinfunction "GND_60_60") (pintype "passive"))
      (node (ref "U1") (pin "61") (pinfunction "GND_61_61") (pintype "passive"))
      (node (ref "U1") (pin "62") (pinfunction "GND_62_62") (pintype "passive"))
      (node (ref "U1") (pin "63") (pinfunction "GND_63_63") (pintype "passive"))
      (node (ref "U1") (pin "64") (pinfunction "GND_64_64") (pintype "passive"))
      (node (ref "U1") (pin "65") (pinfunction "GND_65_65") (pintype "passive"))
      (node (ref "U1") (pin "66") (pinfunction "GND_66_66") (pintype "passive"))
      (node (ref "U1") (pin "67") (pinfunction "GND_67_67") (pintype "passive"))
      (node (ref "U1") (pin "68") (pinfunction "GND_68_68") (pintype "passive"))
      (node (ref "U1") (pin "69") (pinfunction "GND_69_69") (pintype "passive"))
      (node (ref "U1") (pin "70") (pinfunction "GND_70_70") (pintype "passive"))
      (node (ref "U1") (pin "71") (pinfunction "GND_71_71") (pintype "passive"))
      (node (ref "U1") (pin "72") (pinfunction "GND_72_72") (pintype "passive"))
      (node (ref "U1") (pin "73") (pinfunction "GND_73_73") (pintype "passive"))
      (node (ref "U2") (pin "13") (pinfunction "GND_13") (pintype "passive"))
      (node (ref "U2") (pin "21") (pinfunction "GND_21") (pintype "passive"))
      (node (ref "U2") (pin "3") (pinfunction "GND_3") (pintype "passive"))
      (node (ref "U3") (pin "2") (pinfunction "GND_2") (pintype "power_in"))
      (node (ref "U3") (pin "4") (pinfunction "GND_4") (pintype "power_in"))
    )
    (net (code "64") (name "Net-(CON1-CC1)") (class "Default")
      (node (ref "CON1") (pin "A5") (pinfunction "CC1_A5") (pintype "passive"))
      (node (ref "R9") (pin "3") (pinfunction "3_3") (pintype "passive"))
    )
    (net (code "65") (name "Net-(CON1-CC2)") (class "Default")
      (node (ref "CON1") (pin "B5") (pinfunction "CC2_B5") (pintype "passive"))
      (node (ref "R8") (pin "3") (pinfunction "3_3") (pintype "passive"))
    )
    (net (code "66") (name "Net-(CON2-CC1)") (class "Default")
      (node (ref "CON2") (pin "A5") (pinfunction "CC1_A5") (pintype "passive"))
      (node (ref "R13") (pin "3") (pinfunction "3_3") (pintype "passive"))
    )
    (net (code "67") (name "Net-(CON2-CC2)") (class "Default")
      (node (ref "CON2") (pin "B5") (pinfunction "CC2_B5") (pintype "passive"))
      (node (ref "R12") (pin "3") (pinfunction "3_3") (pintype "passive"))
    )
    (net (code "68") (name "Net-(Q1-B)") (class "Default")
      (node (ref "Q1") (pin "1") (pinfunction "B_1") (pintype "passive"))
      (node (ref "R14") (pin "2") (pinfunction "2_2") (pintype "passive"))
    )
    (net (code "69") (name "Net-(Q2-B)") (class "Default")
      (node (ref "Q2") (pin "1") (pinfunction "B_1") (pintype "passive"))
      (node (ref "R16") (pin "2") (pinfunction "2_2") (pintype "passive"))
    )
    (net (code "70") (name "Net-(U2-CBUS0)") (class "Default")
      (node (ref "R7") (pin "3") (pinfunction "3_3") (pintype "passive"))
      (node (ref "U2") (pin "15") (pinfunction "CBUS0_15") (pintype "passive"))
    )
    (net (code "71") (name "Net-(U2-~{RESET})") (class "Default")
      (node (ref "C8") (pin "1") (pinfunction "1_1") (pintype "passive"))
      (node (ref "R6") (pin "3") (pinfunction "3_3") (pintype "passive"))
      (node (ref "U2") (pin "11") (pinfunction "~{RESET}_11") (pintype "passive"))
    )
    (net (code "72") (name "unconnected-(CON1-SBU1-PadA8)") (class "Default")
      (node (ref "CON1") (pin "A8") (pinfunction "SBU1_A8") (pintype "passive+no_connect"))
    )
    (net (code "73") (name "unconnected-(CON1-SBU2-PadB8)") (class "Default")
      (node (ref "CON1") (pin "B8") (pinfunction "SBU2_B8") (pintype "passive+no_connect"))
    )
    (net (code "74") (name "unconnected-(CON2-SBU1-PadA8)") (class "Default")
      (node (ref "CON2") (pin "A8") (pinfunction "SBU1_A8") (pintype "passive+no_connect"))
    )
    (net (code "75") (name "unconnected-(CON2-SBU2-PadB8)") (class "Default")
      (node (ref "CON2") (pin "B8") (pinfunction "SBU2_B8") (pintype "passive+no_connect"))
    )
    (net (code "76") (name "unconnected-(J1-Pad24)") (class "Default")
      (node (ref "J1") (pin "24") (pinfunction "24_24") (pintype "passive+no_connect"))
    )
    (net (code "77") (name "unconnected-(U2-CBUS1-Pad14)") (class "Default")
      (node (ref "U2") (pin "14") (pinfunction "CBUS1_14") (pintype "passive+no_connect"))
    )
    (net (code "78") (name "unconnected-(U2-CBUS2-Pad7)") (class "Default")
      (node (ref "U2") (pin "7") (pinfunction "CBUS2_7") (pintype "passive+no_connect"))
    )
    (net (code "79") (name "unconnected-(U2-~{CTS}-Pad6)") (class "Default")
      (node (ref "U2") (pin "6") (pinfunction "~{CTS}_6") (pintype "passive+no_connect"))
    )
    (net (code "80") (name "unconnected-(U2-~{DCD}-Pad5)") (class "Default")
      (node (ref "U2") (pin "5") (pinfunction "~{DCD}_5") (pintype "passive+no_connect"))
    )
    (net (code "81") (name "unconnected-(U2-~{DSR}-Pad4)") (class "Default")
      (node (ref "U2") (pin "4") (pinfunction "~{DSR}_4") (pintype "passive+no_connect"))
    )
    (net (code "82") (name "unconnected-(U2-~{RI}-Pad2)") (class "Default")
      (node (ref "U2") (pin "2") (pinfunction "~{RI}_2") (pintype "passive+no_connect"))
    )
  )
)
